# CAN_ProtoBoard.net
KiCad netlist of a schematic drawn in EAGLE
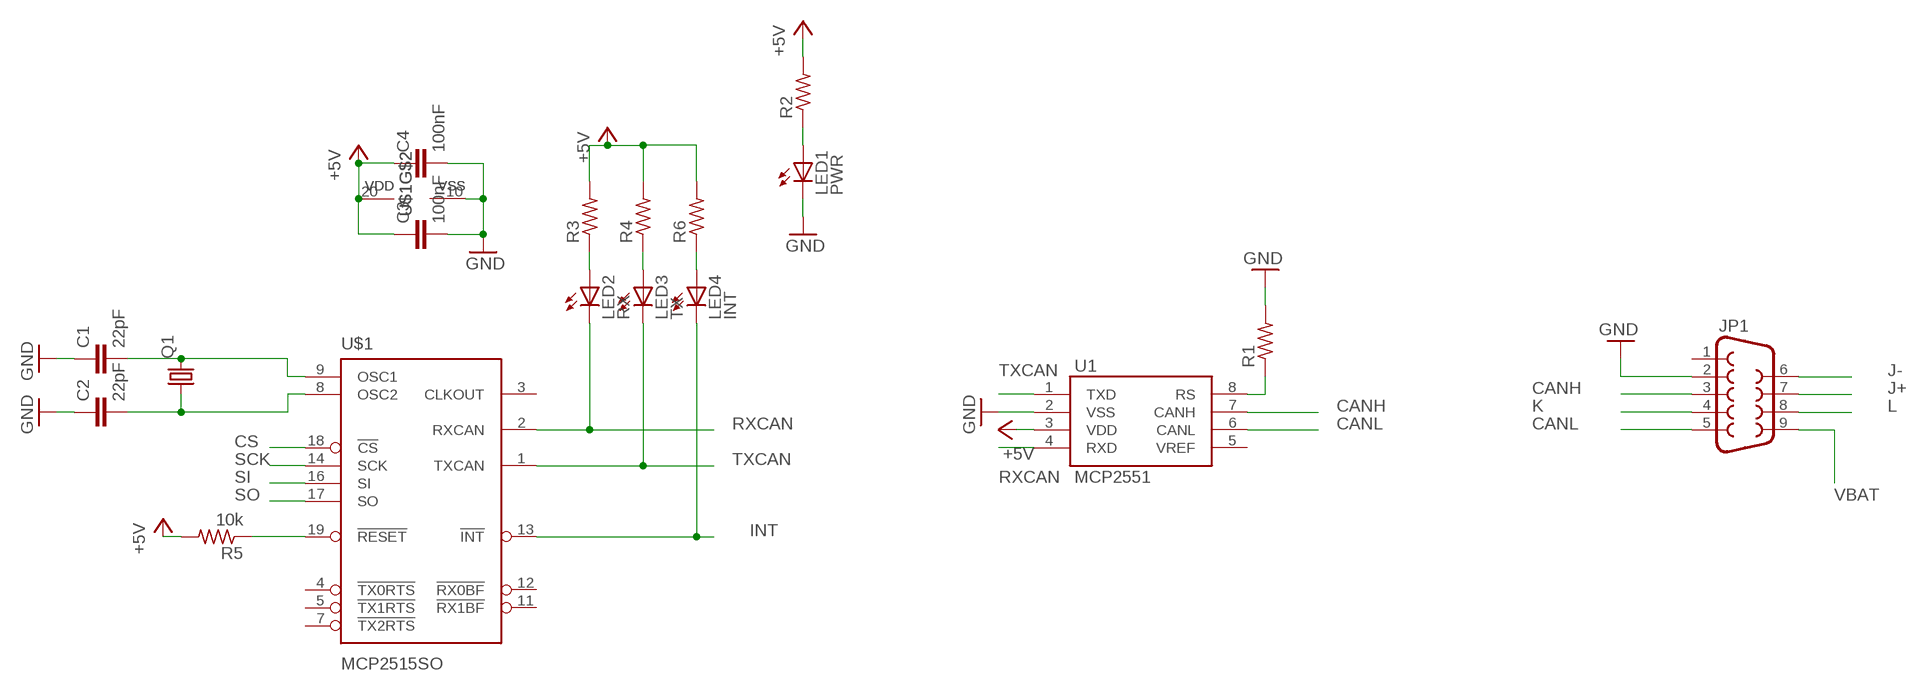
[diagram p0: schematic, sheet 1]

(export (version "E")
  (design (tool "Eeschema 10.0.6"))
  (components
    (comp (ref "C1")
      (value "22pF")
      (footprint "eagle-import:C0805K")
      (libsource (lib "eagle-import") (part "C-EUC0805K"))
    )
    (comp (ref "C2")
      (value "22pF")
      (footprint "eagle-import:C0805K")
      (libsource (lib "eagle-import") (part "C-EUC0805K"))
    )
    (comp (ref "C3")
      (value "100nF")
      (footprint "eagle-import:C0805K")
      (libsource (lib "eagle-import") (part "C-EUC0805K"))
    )
    (comp (ref "C4")
      (value "100nF")
      (footprint "eagle-import:C0805K")
      (libsource (lib "eagle-import") (part "C-EUC0805K"))
    )
    (comp (ref "JP1")
      (value "DB9MALE")
      (footprint "eagle-import:DB9_MALE")
      (libsource (lib "eagle-import") (part "DB9MALE"))
    )
    (comp (ref "LED1")
      (value "PWR")
      (footprint "eagle-import:CHIPLED_0805")
      (libsource (lib "eagle-import") (part "LEDCHIPLED_0805"))
    )
    (comp (ref "LED2")
      (value "RX")
      (footprint "eagle-import:CHIPLED_0805")
      (libsource (lib "eagle-import") (part "LEDCHIPLED_0805"))
    )
    (comp (ref "LED3")
      (value "TX")
      (footprint "eagle-import:CHIPLED_0805")
      (libsource (lib "eagle-import") (part "LEDCHIPLED_0805"))
    )
    (comp (ref "LED4")
      (value "INT")
      (footprint "eagle-import:CHIPLED_0805")
      (libsource (lib "eagle-import") (part "LEDCHIPLED_0805"))
    )
    (comp (ref "Q1")
      (value "CRYSTALHC49S")
      (footprint "eagle-import:HC49_S")
      (libsource (lib "eagle-import") (part "CRYSTALHC49S"))
    )
    (comp (ref "R1")
      (value "R-US_R0805")
      (footprint "eagle-import:R0805")
      (libsource (lib "eagle-import") (part "R-US_R0805"))
    )
    (comp (ref "R2")
      (value "R-US_R0805")
      (footprint "eagle-import:R0805")
      (libsource (lib "eagle-import") (part "R-US_R0805"))
    )
    (comp (ref "R3")
      (value "R-US_R0805")
      (footprint "eagle-import:R0805")
      (libsource (lib "eagle-import") (part "R-US_R0805"))
    )
    (comp (ref "R4")
      (value "R-US_R0805")
      (footprint "eagle-import:R0805")
      (libsource (lib "eagle-import") (part "R-US_R0805"))
    )
    (comp (ref "R5")
      (value "10k")
      (footprint "eagle-import:R0805")
      (libsource (lib "eagle-import") (part "R-US_R0805"))
    )
    (comp (ref "R6")
      (value "R-US_R0805")
      (footprint "eagle-import:R0805")
      (libsource (lib "eagle-import") (part "R-US_R0805"))
    )
    (comp (ref "U$1")
      (value "MCP2515SO")
      (footprint "eagle-import:TSSOP20")
      (libsource (lib "eagle-import") (part "MCP2515SO"))
    )
    (comp (ref "U1")
      (value "MCP2551")
      (footprint "eagle-import:SO08")
      (libsource (lib "eagle-import") (part "MCP2551"))
    )
  )
  (nets
    (net (code "1") (name "+5V") (class "Default")
      (node (ref "C3") (pin "1") (pinfunction "1_1") (pintype "passive"))
      (node (ref "C4") (pin "1") (pinfunction "1_1") (pintype "passive"))
      (node (ref "R2") (pin "2") (pinfunction "2_2") (pintype "passive"))
      (node (ref "R3") (pin "2") (pinfunction "2_2") (pintype "passive"))
      (node (ref "R4") (pin "2") (pinfunction "2_2") (pintype "passive"))
      (node (ref "R5") (pin "2") (pinfunction "2_2") (pintype "passive"))
      (node (ref "R6") (pin "2") (pinfunction "2_2") (pintype "passive"))
      (node (ref "U$1") (pin "20") (pinfunction "VDD_20") (pintype "power_in"))
      (node (ref "U1") (pin "3") (pinfunction "VDD_3") (pintype "bidirectional"))
    )
    (net (code "2") (name "/CANH") (class "Default")
      (node (ref "JP1") (pin "3") (pinfunction "3_3") (pintype "passive"))
      (node (ref "U1") (pin "7") (pinfunction "CANH_7") (pintype "bidirectional"))
    )
    (net (code "3") (name "/CANL") (class "Default")
      (node (ref "JP1") (pin "5") (pinfunction "5_5") (pintype "passive"))
      (node (ref "U1") (pin "6") (pinfunction "CANL_6") (pintype "bidirectional"))
    )
    (net (code "4") (name "/CS") (class "Default")
      (node (ref "U$1") (pin "18") (pinfunction "~{CS}_18") (pintype "input"))
    )
    (net (code "5") (name "/INT") (class "Default")
      (node (ref "LED4") (pin "C") (pinfunction "C_C") (pintype "passive"))
      (node (ref "U$1") (pin "13") (pinfunction "~{INT}_13") (pintype "output"))
    )
    (net (code "6") (name "/J+") (class "Default")
      (node (ref "JP1") (pin "7") (pinfunction "7_7") (pintype "passive"))
    )
    (net (code "7") (name "/J-") (class "Default")
      (node (ref "JP1") (pin "6") (pinfunction "6_6") (pintype "passive"))
    )
    (net (code "8") (name "/K") (class "Default")
      (node (ref "JP1") (pin "4") (pinfunction "4_4") (pintype "passive"))
    )
    (net (code "9") (name "/L") (class "Default")
      (node (ref "JP1") (pin "8") (pinfunction "8_8") (pintype "passive"))
    )
    (net (code "10") (name "/RXCAN") (class "Default")
      (node (ref "LED2") (pin "C") (pinfunction "C_C") (pintype "passive"))
      (node (ref "U$1") (pin "2") (pinfunction "RXCAN_2") (pintype "input"))
      (node (ref "U1") (pin "4") (pinfunction "RXD_4") (pintype "bidirectional"))
    )
    (net (code "11") (name "/SCK") (class "Default")
      (node (ref "U$1") (pin "14") (pinfunction "SCK_14") (pintype "input"))
    )
    (net (code "12") (name "/SI") (class "Default")
      (node (ref "U$1") (pin "16") (pinfunction "SI_16") (pintype "input"))
    )
    (net (code "13") (name "/SO") (class "Default")
      (node (ref "U$1") (pin "17") (pinfunction "SO_17") (pintype "output"))
    )
    (net (code "14") (name "/TXCAN") (class "Default")
      (node (ref "LED3") (pin "C") (pinfunction "C_C") (pintype "passive"))
      (node (ref "U$1") (pin "1") (pinfunction "TXCAN_1") (pintype "output"))
      (node (ref "U1") (pin "1") (pinfunction "TXD_1") (pintype "bidirectional"))
    )
    (net (code "15") (name "/VBAT") (class "Default")
      (node (ref "JP1") (pin "9") (pinfunction "9_9") (pintype "passive"))
    )
    (net (code "16") (name "GND") (class "Default")
      (node (ref "C1") (pin "1") (pinfunction "1_1") (pintype "passive"))
      (node (ref "C2") (pin "1") (pinfunction "1_1") (pintype "passive"))
      (node (ref "C3") (pin "2") (pinfunction "2_2") (pintype "passive"))
      (node (ref "C4") (pin "2") (pinfunction "2_2") (pintype "passive"))
      (node (ref "JP1") (pin "2") (pinfunction "2_2") (pintype "passive"))
      (node (ref "LED1") (pin "C") (pinfunction "C_C") (pintype "passive"))
      (node (ref "R1") (pin "2") (pinfunction "2_2") (pintype "passive"))
      (node (ref "U$1") (pin "10") (pinfunction "VSS_10") (pintype "power_in"))
      (node (ref "U1") (pin "2") (pinfunction "VSS_2") (pintype "bidirectional"))
    )
    (net (code "17") (name "Net-(LED1-PadA)") (class "Default")
      (node (ref "LED1") (pin "A") (pinfunction "A_A") (pintype "passive"))
      (node (ref "R2") (pin "1") (pinfunction "1_1") (pintype "passive"))
    )
    (net (code "18") (name "Net-(LED2-PadA)") (class "Default")
      (node (ref "LED2") (pin "A") (pinfunction "A_A") (pintype "passive"))
      (node (ref "R3") (pin "1") (pinfunction "1_1") (pintype "passive"))
    )
    (net (code "19") (name "Net-(LED3-PadA)") (class "Default")
      (node (ref "LED3") (pin "A") (pinfunction "A_A") (pintype "passive"))
      (node (ref "R4") (pin "1") (pinfunction "1_1") (pintype "passive"))
    )
    (net (code "20") (name "Net-(LED4-PadA)") (class "Default")
      (node (ref "LED4") (pin "A") (pinfunction "A_A") (pintype "passive"))
      (node (ref "R6") (pin "1") (pinfunction "1_1") (pintype "passive"))
    )
    (net (code "21") (name "Net-(U$1A-OSC1)") (class "Default")
      (node (ref "C1") (pin "2") (pinfunction "2_2") (pintype "passive"))
      (node (ref "Q1") (pin "2") (pinfunction "2_2") (pintype "passive"))
      (node (ref "U$1") (pin "9") (pinfunction "OSC1_9") (pintype "input"))
    )
    (net (code "22") (name "Net-(U$1A-OSC2)") (class "Default")
      (node (ref "C2") (pin "2") (pinfunction "2_2") (pintype "passive"))
      (node (ref "Q1") (pin "1") (pinfunction "1_1") (pintype "passive"))
      (node (ref "U$1") (pin "8") (pinfunction "OSC2_8") (pintype "output"))
    )
    (net (code "23") (name "Net-(U$1A-~{RESET})") (class "Default")
      (node (ref "R5") (pin "1") (pinfunction "1_1") (pintype "passive"))
      (node (ref "U$1") (pin "19") (pinfunction "~{RESET}_19") (pintype "input"))
    )
    (net (code "24") (name "Net-(U1-RS)") (class "Default")
      (node (ref "R1") (pin "1") (pinfunction "1_1") (pintype "passive"))
      (node (ref "U1") (pin "8") (pinfunction "RS_8") (pintype "bidirectional"))
    )
    (net (code "25") (name "unconnected-(JP1-Pad1)") (class "Default")
      (node (ref "JP1") (pin "1") (pinfunction "1_1") (pintype "passive"))
    )
    (net (code "26") (name "unconnected-(U$1A-CLKOUT-Pad3)") (class "Default")
      (node (ref "U$1") (pin "3") (pinfunction "CLKOUT_3") (pintype "output"))
    )
    (net (code "27") (name "unconnected-(U$1A-~{RX0BF}-Pad12)") (class "Default")
      (node (ref "U$1") (pin "12") (pinfunction "~{RX0BF}_12") (pintype "output"))
    )
    (net (code "28") (name "unconnected-(U$1A-~{RX1BF}-Pad11)") (class "Default")
      (node (ref "U$1") (pin "11") (pinfunction "~{RX1BF}_11") (pintype "output"))
    )
    (net (code "29") (name "unconnected-(U$1A-~{TX0RTS}-Pad4)") (class "Default")
      (node (ref "U$1") (pin "4") (pinfunction "~{TX0RTS}_4") (pintype "input"))
    )
    (net (code "30") (name "unconnected-(U$1A-~{TX1RTS}-Pad5)") (class "Default")
      (node (ref "U$1") (pin "5") (pinfunction "~{TX1RTS}_5") (pintype "input"))
    )
    (net (code "31") (name "unconnected-(U$1A-~{TX2RTS}-Pad7)") (class "Default")
      (node (ref "U$1") (pin "7") (pinfunction "~{TX2RTS}_7") (pintype "input"))
    )
    (net (code "32") (name "unconnected-(U1-VREF-Pad5)") (class "Default")
      (node (ref "U1") (pin "5") (pinfunction "VREF_5") (pintype "bidirectional"))
    )
  )
)
